# ROM-el_HN61256_v2_TH.net
KiCad netlist of a schematic drawn in EAGLE
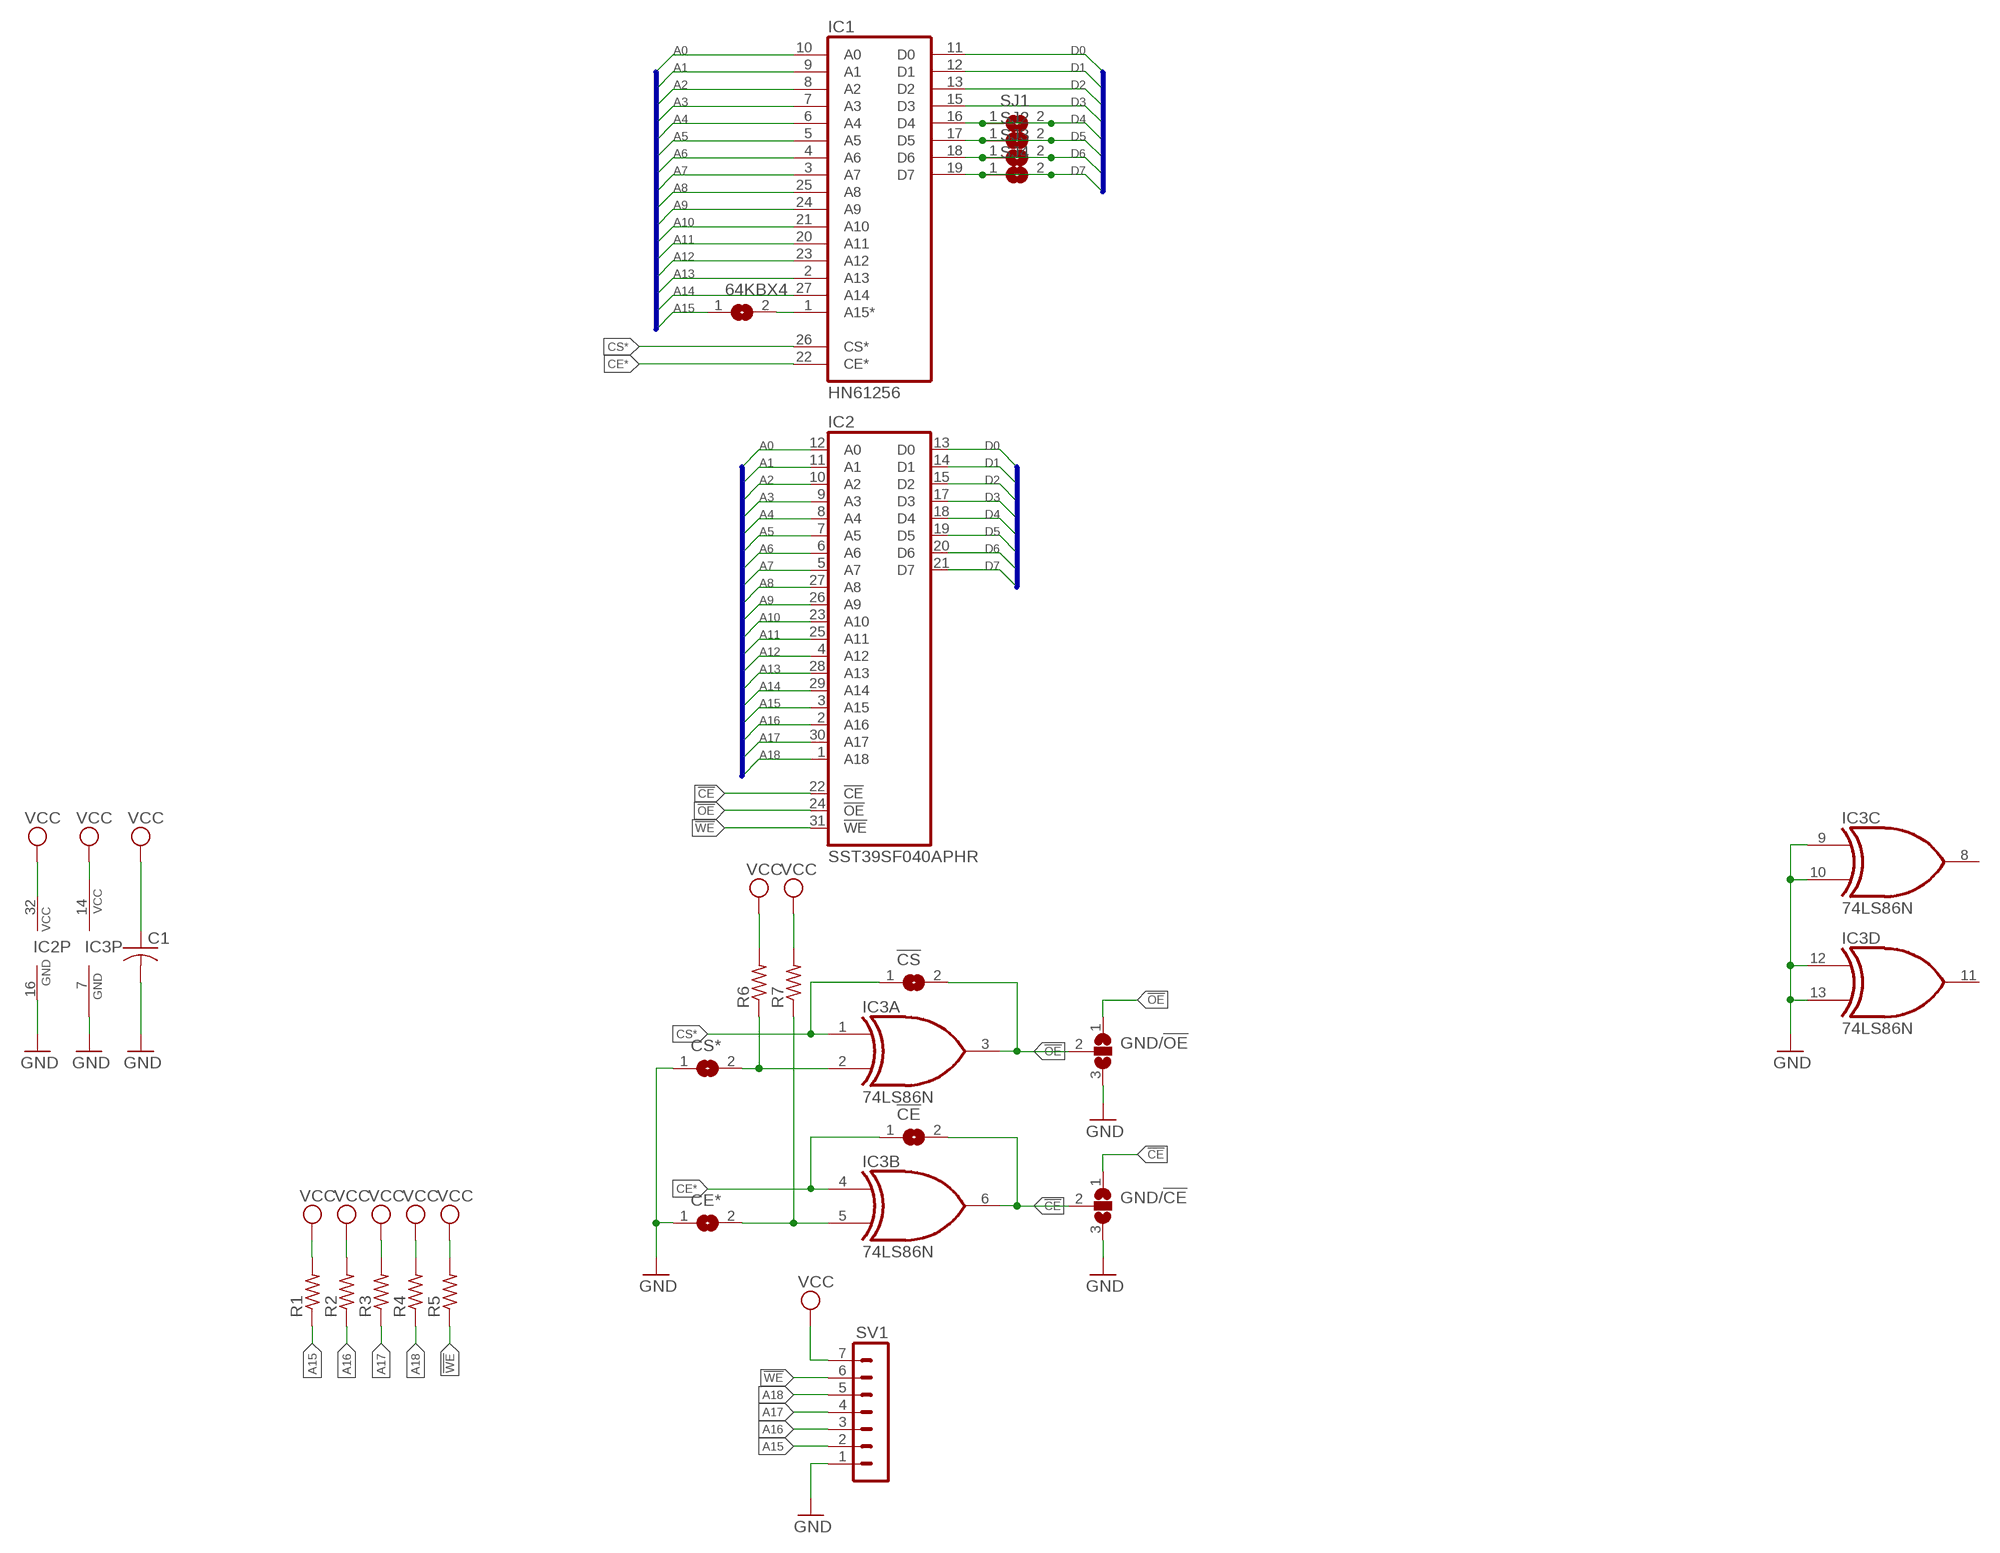
[diagram p0: schematic, sheet 1]

(export (version "E")
  (design (tool "Eeschema 10.0.6"))
  (components
    (comp (ref "!CE") (value "SJ") (footprint "eagle-import:SJ") (libsource (lib "eagle-import") (part "SJ")))
    (comp (ref "!CS") (value "SJ") (footprint "eagle-import:SJ") (libsource (lib "eagle-import") (part "SJ")))
    (comp (ref "64KBX4")
      (value "SJ")
      (footprint "eagle-import:SJ")
      (libsource (lib "eagle-import") (part "SJ"))
    )
    (comp (ref "C1")
      (value "C-US025-025X050")
      (footprint "eagle-import:C025-025X050")
      (libsource (lib "eagle-import") (part "C-US025-025X050"))
    )
    (comp (ref "CE*") (value "SJ") (footprint "eagle-import:SJ") (libsource (lib "eagle-import") (part "SJ")))
    (comp (ref "CS*") (value "SJ") (footprint "eagle-import:SJ") (libsource (lib "eagle-import") (part "SJ")))
    (comp (ref "GND/!CE")
      (value "SJ2W")
      (footprint "eagle-import:SJ_2")
      (libsource (lib "eagle-import") (part "SJ2W"))
    )
    (comp (ref "GND/!OE")
      (value "SJ2W")
      (footprint "eagle-import:SJ_2")
      (libsource (lib "eagle-import") (part "SJ2W"))
    )
    (comp (ref "IC1")
      (value "HN61256")
      (footprint "eagle-import:DIL28-6")
      (libsource (lib "eagle-import") (part "HN61256"))
    )
    (comp (ref "IC2")
      (value "SST39SF040APHR")
      (footprint "eagle-import:DIL32-RP")
      (libsource (lib "eagle-import") (part "SST39SF040APHR"))
    )
    (comp (ref "IC3")
      (value "74LS86N")
      (footprint "eagle-import:DIL14-RP")
      (libsource (lib "eagle-import") (part "7486NLS"))
    )
    (comp (ref "R1")
      (value "R-US_0204/5")
      (footprint "eagle-import:0204_5")
      (libsource (lib "eagle-import") (part "R-US_0204/5"))
    )
    (comp (ref "R2")
      (value "R-US_0204/5")
      (footprint "eagle-import:0204_5")
      (libsource (lib "eagle-import") (part "R-US_0204/5"))
    )
    (comp (ref "R3")
      (value "R-US_0204/5")
      (footprint "eagle-import:0204_5")
      (libsource (lib "eagle-import") (part "R-US_0204/5"))
    )
    (comp (ref "R4")
      (value "R-US_0204/5")
      (footprint "eagle-import:0204_5")
      (libsource (lib "eagle-import") (part "R-US_0204/5"))
    )
    (comp (ref "R5")
      (value "R-US_0204/5")
      (footprint "eagle-import:0204_5")
      (libsource (lib "eagle-import") (part "R-US_0204/5"))
    )
    (comp (ref "R6")
      (value "R-US_0204/5")
      (footprint "eagle-import:0204_5")
      (libsource (lib "eagle-import") (part "R-US_0204/5"))
    )
    (comp (ref "R7")
      (value "R-US_0204/5")
      (footprint "eagle-import:0204_5")
      (libsource (lib "eagle-import") (part "R-US_0204/5"))
    )
    (comp (ref "SJ1") (value "SJ") (footprint "eagle-import:SJ") (libsource (lib "eagle-import") (part "SJ")))
    (comp (ref "SJ2") (value "SJ") (footprint "eagle-import:SJ") (libsource (lib "eagle-import") (part "SJ")))
    (comp (ref "SJ3") (value "SJ") (footprint "eagle-import:SJ") (libsource (lib "eagle-import") (part "SJ")))
    (comp (ref "SJ4") (value "SJ") (footprint "eagle-import:SJ") (libsource (lib "eagle-import") (part "SJ")))
    (comp (ref "SV1")
      (value "MA07-1")
      (footprint "eagle-import:MA07-1")
      (libsource (lib "eagle-import") (part "MA07-1"))
    )
  )
  (nets
    (net (code "1") (name "/A0") (class "Default")
      (node (ref "IC1") (pin "10") (pinfunction "A0_10") (pintype "input"))
      (node (ref "IC2") (pin "12") (pinfunction "A0_12") (pintype "input"))
    )
    (net (code "2") (name "/A1") (class "Default")
      (node (ref "IC1") (pin "9") (pinfunction "A1_9") (pintype "input"))
      (node (ref "IC2") (pin "11") (pinfunction "A1_11") (pintype "input"))
    )
    (net (code "3") (name "/A2") (class "Default")
      (node (ref "IC1") (pin "8") (pinfunction "A2_8") (pintype "input"))
      (node (ref "IC2") (pin "10") (pinfunction "A2_10") (pintype "input"))
    )
    (net (code "4") (name "/A3") (class "Default")
      (node (ref "IC1") (pin "7") (pinfunction "A3_7") (pintype "input"))
      (node (ref "IC2") (pin "9") (pinfunction "A3_9") (pintype "input"))
    )
    (net (code "5") (name "/A4") (class "Default")
      (node (ref "IC1") (pin "6") (pinfunction "A4_6") (pintype "input"))
      (node (ref "IC2") (pin "8") (pinfunction "A4_8") (pintype "input"))
    )
    (net (code "6") (name "/A5") (class "Default")
      (node (ref "IC1") (pin "5") (pinfunction "A5_5") (pintype "input"))
      (node (ref "IC2") (pin "7") (pinfunction "A5_7") (pintype "input"))
    )
    (net (code "7") (name "/A6") (class "Default")
      (node (ref "IC1") (pin "4") (pinfunction "A6_4") (pintype "input"))
      (node (ref "IC2") (pin "6") (pinfunction "A6_6") (pintype "input"))
    )
    (net (code "8") (name "/A7") (class "Default")
      (node (ref "IC1") (pin "3") (pinfunction "A7_3") (pintype "input"))
      (node (ref "IC2") (pin "5") (pinfunction "A7_5") (pintype "input"))
    )
    (net (code "9") (name "/A8") (class "Default")
      (node (ref "IC1") (pin "25") (pinfunction "A8_25") (pintype "input"))
      (node (ref "IC2") (pin "27") (pinfunction "A8_27") (pintype "input"))
    )
    (net (code "10") (name "/A9") (class "Default")
      (node (ref "IC1") (pin "24") (pinfunction "A9_24") (pintype "input"))
      (node (ref "IC2") (pin "26") (pinfunction "A9_26") (pintype "input"))
    )
    (net (code "11") (name "/A10") (class "Default")
      (node (ref "IC1") (pin "21") (pinfunction "A10_21") (pintype "input"))
      (node (ref "IC2") (pin "23") (pinfunction "A10_23") (pintype "input"))
    )
    (net (code "12") (name "/A11") (class "Default")
      (node (ref "IC1") (pin "20") (pinfunction "A11_20") (pintype "input"))
      (node (ref "IC2") (pin "25") (pinfunction "A11_25") (pintype "input"))
    )
    (net (code "13") (name "/A12") (class "Default")
      (node (ref "IC1") (pin "23") (pinfunction "A12_23") (pintype "input"))
      (node (ref "IC2") (pin "4") (pinfunction "A12_4") (pintype "input"))
    )
    (net (code "14") (name "/A13") (class "Default")
      (node (ref "IC1") (pin "2") (pinfunction "A13_2") (pintype "input"))
      (node (ref "IC2") (pin "28") (pinfunction "A13_28") (pintype "input"))
    )
    (net (code "15") (name "/A14") (class "Default")
      (node (ref "IC1") (pin "27") (pinfunction "A14_27") (pintype "input"))
      (node (ref "IC2") (pin "29") (pinfunction "A14_29") (pintype "input"))
    )
    (net (code "16") (name "/D0") (class "Default")
      (node (ref "IC1") (pin "11") (pinfunction "D0_11") (pintype "bidirectional"))
      (node (ref "IC2") (pin "13") (pinfunction "D0_13") (pintype "bidirectional"))
    )
    (net (code "17") (name "/D1") (class "Default")
      (node (ref "IC1") (pin "12") (pinfunction "D1_12") (pintype "bidirectional"))
      (node (ref "IC2") (pin "14") (pinfunction "D1_14") (pintype "bidirectional"))
    )
    (net (code "18") (name "/D2") (class "Default")
      (node (ref "IC1") (pin "13") (pinfunction "D2_13") (pintype "bidirectional"))
      (node (ref "IC2") (pin "15") (pinfunction "D2_15") (pintype "bidirectional"))
    )
    (net (code "19") (name "/D3") (class "Default")
      (node (ref "IC1") (pin "15") (pinfunction "D3_15") (pintype "bidirectional"))
      (node (ref "IC2") (pin "17") (pinfunction "D3_17") (pintype "bidirectional"))
    )
    (net (code "20") (name "/D4") (class "Default")
      (node (ref "IC1") (pin "16") (pinfunction "D4_16") (pintype "bidirectional"))
      (node (ref "IC2") (pin "18") (pinfunction "D4_18") (pintype "bidirectional"))
      (node (ref "SJ1") (pin "1") (pinfunction "1_1") (pintype "passive"))
      (node (ref "SJ1") (pin "2") (pinfunction "2_2") (pintype "passive"))
    )
    (net (code "21") (name "/D5") (class "Default")
      (node (ref "IC1") (pin "17") (pinfunction "D5_17") (pintype "bidirectional"))
      (node (ref "IC2") (pin "19") (pinfunction "D5_19") (pintype "bidirectional"))
      (node (ref "SJ2") (pin "1") (pinfunction "1_1") (pintype "passive"))
      (node (ref "SJ2") (pin "2") (pinfunction "2_2") (pintype "passive"))
    )
    (net (code "22") (name "/D6") (class "Default")
      (node (ref "IC1") (pin "18") (pinfunction "D6_18") (pintype "bidirectional"))
      (node (ref "IC2") (pin "20") (pinfunction "D6_20") (pintype "bidirectional"))
      (node (ref "SJ3") (pin "1") (pinfunction "1_1") (pintype "passive"))
      (node (ref "SJ3") (pin "2") (pinfunction "2_2") (pintype "passive"))
    )
    (net (code "23") (name "/D7") (class "Default")
      (node (ref "IC1") (pin "19") (pinfunction "D7_19") (pintype "bidirectional"))
      (node (ref "IC2") (pin "21") (pinfunction "D7_21") (pintype "bidirectional"))
      (node (ref "SJ4") (pin "1") (pinfunction "1_1") (pintype "passive"))
      (node (ref "SJ4") (pin "2") (pinfunction "2_2") (pintype "passive"))
    )
    (net (code "24") (name "/~{CE}") (class "Default")
      (node (ref "!CE") (pin "2") (pinfunction "2_2") (pintype "passive"))
      (node (ref "GND/!CE") (pin "1") (pinfunction "1_1") (pintype "passive"))
      (node (ref "GND/!CE") (pin "2") (pinfunction "2_2") (pintype "passive"))
      (node (ref "IC2") (pin "22") (pinfunction "~{CE}_22") (pintype "input"))
      (node (ref "IC3") (pin "6") (pinfunction "O_6") (pintype "output"))
    )
    (net (code "25") (name "/~{OE}") (class "Default")
      (node (ref "!CS") (pin "2") (pinfunction "2_2") (pintype "passive"))
      (node (ref "GND/!OE") (pin "1") (pinfunction "1_1") (pintype "passive"))
      (node (ref "GND/!OE") (pin "2") (pinfunction "2_2") (pintype "passive"))
      (node (ref "IC2") (pin "24") (pinfunction "~{OE}_24") (pintype "input"))
      (node (ref "IC3") (pin "3") (pinfunction "O_3") (pintype "output"))
    )
    (net (code "26") (name "/~{WE}") (class "Default")
      (node (ref "IC2") (pin "31") (pinfunction "~{WE}_31") (pintype "input"))
      (node (ref "R5") (pin "1") (pinfunction "1_1") (pintype "passive"))
      (node (ref "SV1") (pin "6") (pinfunction "6_6") (pintype "passive"))
    )
    (net (code "27") (name "A15") (class "Default")
      (node (ref "64KBX4") (pin "1") (pinfunction "1_1") (pintype "passive"))
      (node (ref "IC2") (pin "3") (pinfunction "A15_3") (pintype "input"))
      (node (ref "R1") (pin "1") (pinfunction "1_1") (pintype "passive"))
      (node (ref "SV1") (pin "2") (pinfunction "2_2") (pintype "passive"))
    )
    (net (code "28") (name "A16") (class "Default")
      (node (ref "IC2") (pin "2") (pinfunction "A16_2") (pintype "input"))
      (node (ref "R2") (pin "1") (pinfunction "1_1") (pintype "passive"))
      (node (ref "SV1") (pin "3") (pinfunction "3_3") (pintype "passive"))
    )
    (net (code "29") (name "A17") (class "Default")
      (node (ref "IC2") (pin "30") (pinfunction "A17_30") (pintype "input"))
      (node (ref "R3") (pin "1") (pinfunction "1_1") (pintype "passive"))
      (node (ref "SV1") (pin "4") (pinfunction "4_4") (pintype "passive"))
    )
    (net (code "30") (name "A18") (class "Default")
      (node (ref "IC2") (pin "1") (pinfunction "A18_1") (pintype "input"))
      (node (ref "R4") (pin "1") (pinfunction "1_1") (pintype "passive"))
      (node (ref "SV1") (pin "5") (pinfunction "5_5") (pintype "passive"))
    )
    (net (code "31") (name "CE*") (class "Default")
      (node (ref "!CE") (pin "1") (pinfunction "1_1") (pintype "passive"))
      (node (ref "IC1") (pin "22") (pinfunction "CE*_22") (pintype "input"))
      (node (ref "IC3") (pin "4") (pinfunction "I0_4") (pintype "input"))
    )
    (net (code "32") (name "CS*") (class "Default")
      (node (ref "!CS") (pin "1") (pinfunction "1_1") (pintype "passive"))
      (node (ref "IC1") (pin "26") (pinfunction "CS*_26") (pintype "input"))
      (node (ref "IC3") (pin "1") (pinfunction "I0_1") (pintype "input"))
    )
    (net (code "33") (name "GND") (class "Default")
      (node (ref "C1") (pin "2") (pinfunction "2_2") (pintype "passive"))
      (node (ref "CE*") (pin "1") (pinfunction "1_1") (pintype "passive"))
      (node (ref "CS*") (pin "1") (pinfunction "1_1") (pintype "passive"))
      (node (ref "GND/!CE") (pin "3") (pinfunction "3_3") (pintype "passive"))
      (node (ref "GND/!OE") (pin "3") (pinfunction "3_3") (pintype "passive"))
      (node (ref "IC2") (pin "16") (pinfunction "GND_16") (pintype "power_in"))
      (node (ref "IC3") (pin "10") (pinfunction "I1_10") (pintype "input"))
      (node (ref "IC3") (pin "12") (pinfunction "I0_12") (pintype "input"))
      (node (ref "IC3") (pin "13") (pinfunction "I1_13") (pintype "input"))
      (node (ref "IC3") (pin "7") (pinfunction "GND_7") (pintype "power_in"))
      (node (ref "IC3") (pin "9") (pinfunction "I0_9") (pintype "input"))
      (node (ref "SV1") (pin "1") (pinfunction "1_1") (pintype "passive"))
    )
    (net (code "34") (name "Net-(IC1A-A15*)") (class "Default")
      (node (ref "64KBX4") (pin "2") (pinfunction "2_2") (pintype "passive"))
      (node (ref "IC1") (pin "1") (pinfunction "A15*_1") (pintype "input"))
    )
    (net (code "35") (name "Net-(IC3A-I1)") (class "Default")
      (node (ref "CS*") (pin "2") (pinfunction "2_2") (pintype "passive"))
      (node (ref "IC3") (pin "2") (pinfunction "I1_2") (pintype "input"))
      (node (ref "R6") (pin "1") (pinfunction "1_1") (pintype "passive"))
    )
    (net (code "36") (name "Net-(IC3B-I1)") (class "Default")
      (node (ref "CE*") (pin "2") (pinfunction "2_2") (pintype "passive"))
      (node (ref "IC3") (pin "5") (pinfunction "I1_5") (pintype "input"))
      (node (ref "R7") (pin "1") (pinfunction "1_1") (pintype "passive"))
    )
    (net (code "37") (name "VCC") (class "Default")
      (node (ref "C1") (pin "1") (pinfunction "1_1") (pintype "passive"))
      (node (ref "IC2") (pin "32") (pinfunction "VCC_32") (pintype "power_in"))
      (node (ref "IC3") (pin "14") (pinfunction "VCC_14") (pintype "power_in"))
      (node (ref "R1") (pin "2") (pinfunction "2_2") (pintype "passive"))
      (node (ref "R2") (pin "2") (pinfunction "2_2") (pintype "passive"))
      (node (ref "R3") (pin "2") (pinfunction "2_2") (pintype "passive"))
      (node (ref "R4") (pin "2") (pinfunction "2_2") (pintype "passive"))
      (node (ref "R5") (pin "2") (pinfunction "2_2") (pintype "passive"))
      (node (ref "R6") (pin "2") (pinfunction "2_2") (pintype "passive"))
      (node (ref "R7") (pin "2") (pinfunction "2_2") (pintype "passive"))
      (node (ref "SV1") (pin "7") (pinfunction "7_7") (pintype "passive"))
    )
    (net (code "38") (name "unconnected-(IC3C-O-Pad8)") (class "Default")
      (node (ref "IC3") (pin "8") (pinfunction "O_8") (pintype "output"))
    )
    (net (code "39") (name "unconnected-(IC3D-O-Pad11)") (class "Default")
      (node (ref "IC3") (pin "11") (pinfunction "O_11") (pintype "output"))
    )
  )
)
